# deskaLED.net
KiCad netlist of a schematic drawn in EAGLE
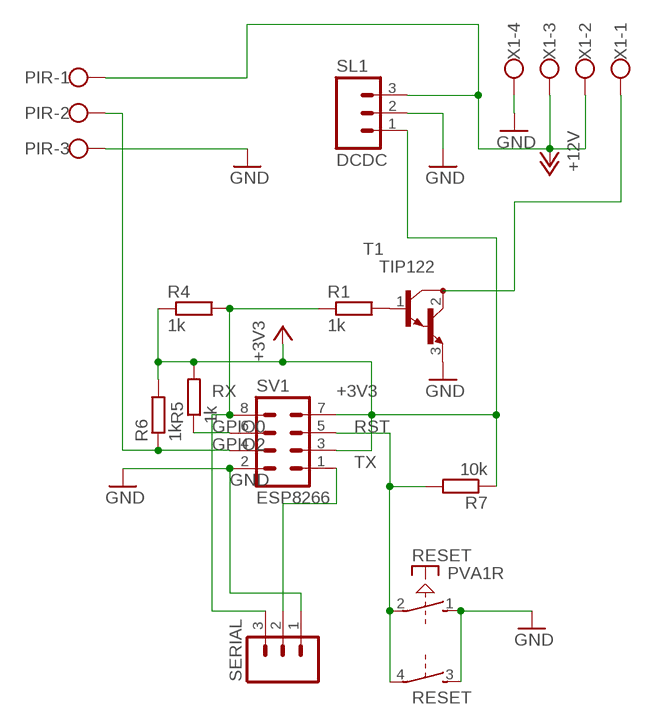
[diagram p0: schematic, sheet 1]

(export (version "E")
  (design (tool "Eeschema 10.0.6"))
  (components
    (comp (ref "PIR")
      (value "W237-103")
      (footprint "eagle-import:W237-103")
      (fields (field (name "MPN") "237-103"))
      (libsource (lib "eagle-import") (part "W237-103"))
    )
    (comp (ref "R1")
      (value "1k")
      (footprint "eagle-import:0207_10")
      (libsource (lib "eagle-import") (part "R-EU_0207/10"))
    )
    (comp (ref "R4")
      (value "1k")
      (footprint "eagle-import:0207_10")
      (libsource (lib "eagle-import") (part "R-EU_0207/10"))
    )
    (comp (ref "R5")
      (value "1k")
      (footprint "eagle-import:0207_10")
      (libsource (lib "eagle-import") (part "R-EU_0207/10"))
    )
    (comp (ref "R6")
      (value "1k")
      (footprint "eagle-import:0207_10")
      (libsource (lib "eagle-import") (part "R-EU_0207/10"))
    )
    (comp (ref "R7")
      (value "10k")
      (footprint "eagle-import:0207_10")
      (libsource (lib "eagle-import") (part "R-EU_0207/10"))
    )
    (comp (ref "RESET")
      (value "PVA1R")
      (footprint "eagle-import:PVA1R")
      (libsource (lib "eagle-import") (part "PVA1R"))
    )
    (comp (ref "SERIAL")
      (value "M03")
      (footprint "eagle-import:03P")
      (libsource (lib "eagle-import") (part "M03"))
    )
    (comp (ref "SL1")
      (value "DCDC")
      (footprint "eagle-import:03P")
      (libsource (lib "eagle-import") (part "M03"))
    )
    (comp (ref "SV1")
      (value "ESP8266")
      (footprint "eagle-import:MA04-2")
      (libsource (lib "eagle-import") (part "MA04-2"))
    )
    (comp (ref "T1")
      (value "TIP122")
      (footprint "eagle-import:TO220")
      (libsource (lib "eagle-import") (part "TIP122"))
    )
    (comp (ref "X1")
      (value "W237-4")
      (footprint "eagle-import:W237-4")
      (libsource (lib "eagle-import") (part "W237-4"))
    )
  )
  (nets
    (net (code "1") (name "+3V3") (class "Default")
      (node (ref "R4") (pin "1") (pinfunction "1_1") (pintype "passive"))
      (node (ref "R5") (pin "2") (pinfunction "2_2") (pintype "passive"))
      (node (ref "R6") (pin "2") (pinfunction "2_2") (pintype "passive"))
      (node (ref "R7") (pin "1") (pinfunction "1_1") (pintype "passive"))
      (node (ref "SL1") (pin "1") (pinfunction "1_1") (pintype "passive"))
      (node (ref "SV1") (pin "3") (pinfunction "3_3") (pintype "passive"))
      (node (ref "SV1") (pin "7") (pinfunction "7_7") (pintype "passive"))
    )
    (net (code "2") (name "+12V") (class "Default")
      (node (ref "PIR") (pin "1") (pinfunction "KL_1") (pintype "passive"))
      (node (ref "SL1") (pin "3") (pinfunction "3_3") (pintype "passive"))
      (node (ref "X1") (pin "2") (pinfunction "KL_2") (pintype "passive"))
      (node (ref "X1") (pin "3") (pinfunction "KL_3") (pintype "passive"))
    )
    (net (code "3") (name "/GPIO0") (class "Default")
      (node (ref "R5") (pin "1") (pinfunction "1_1") (pintype "passive"))
      (node (ref "SV1") (pin "6") (pinfunction "6_6") (pintype "passive"))
    )
    (net (code "4") (name "/GPIO2") (class "Default")
      (node (ref "PIR") (pin "2") (pinfunction "KL_2") (pintype "passive"))
      (node (ref "R6") (pin "1") (pinfunction "1_1") (pintype "passive"))
      (node (ref "SV1") (pin "4") (pinfunction "4_4") (pintype "passive"))
    )
    (net (code "5") (name "/RST") (class "Default")
      (node (ref "R7") (pin "2") (pinfunction "2_2") (pintype "passive"))
      (node (ref "RESET") (pin "2") (pinfunction "P_2") (pintype "passive"))
      (node (ref "RESET") (pin "4") (pinfunction "P_4") (pintype "passive"))
      (node (ref "SV1") (pin "5") (pinfunction "5_5") (pintype "passive"))
    )
    (net (code "6") (name "/RX") (class "Default")
      (node (ref "R1") (pin "1") (pinfunction "1_1") (pintype "passive"))
      (node (ref "R4") (pin "2") (pinfunction "2_2") (pintype "passive"))
      (node (ref "SERIAL") (pin "3") (pinfunction "3_3") (pintype "passive"))
      (node (ref "SV1") (pin "8") (pinfunction "8_8") (pintype "passive"))
    )
    (net (code "7") (name "/TX") (class "Default")
      (node (ref "SERIAL") (pin "2") (pinfunction "2_2") (pintype "passive"))
      (node (ref "SV1") (pin "1") (pinfunction "1_1") (pintype "passive"))
    )
    (net (code "8") (name "GND") (class "Default")
      (node (ref "PIR") (pin "3") (pinfunction "KL_3") (pintype "passive"))
      (node (ref "RESET") (pin "1") (pinfunction "S_1") (pintype "passive"))
      (node (ref "RESET") (pin "3") (pinfunction "S_3") (pintype "passive"))
      (node (ref "SERIAL") (pin "1") (pinfunction "1_1") (pintype "passive"))
      (node (ref "SL1") (pin "2") (pinfunction "2_2") (pintype "passive"))
      (node (ref "SV1") (pin "2") (pinfunction "2_2") (pintype "passive"))
      (node (ref "T1") (pin "3") (pinfunction "E_3") (pintype "passive"))
      (node (ref "X1") (pin "4") (pinfunction "KL_4") (pintype "passive"))
    )
    (net (code "9") (name "Net-(T1-B)") (class "Default")
      (node (ref "R1") (pin "2") (pinfunction "2_2") (pintype "passive"))
      (node (ref "T1") (pin "1") (pinfunction "B_1") (pintype "passive"))
    )
    (net (code "10") (name "Net-(T1-C)") (class "Default")
      (node (ref "T1") (pin "2") (pinfunction "C_2") (pintype "passive"))
      (node (ref "X1") (pin "1") (pinfunction "KL_1") (pintype "passive"))
    )
  )
)
